# electronic_load_chip.net
KiCad netlist of a schematic drawn in EAGLE
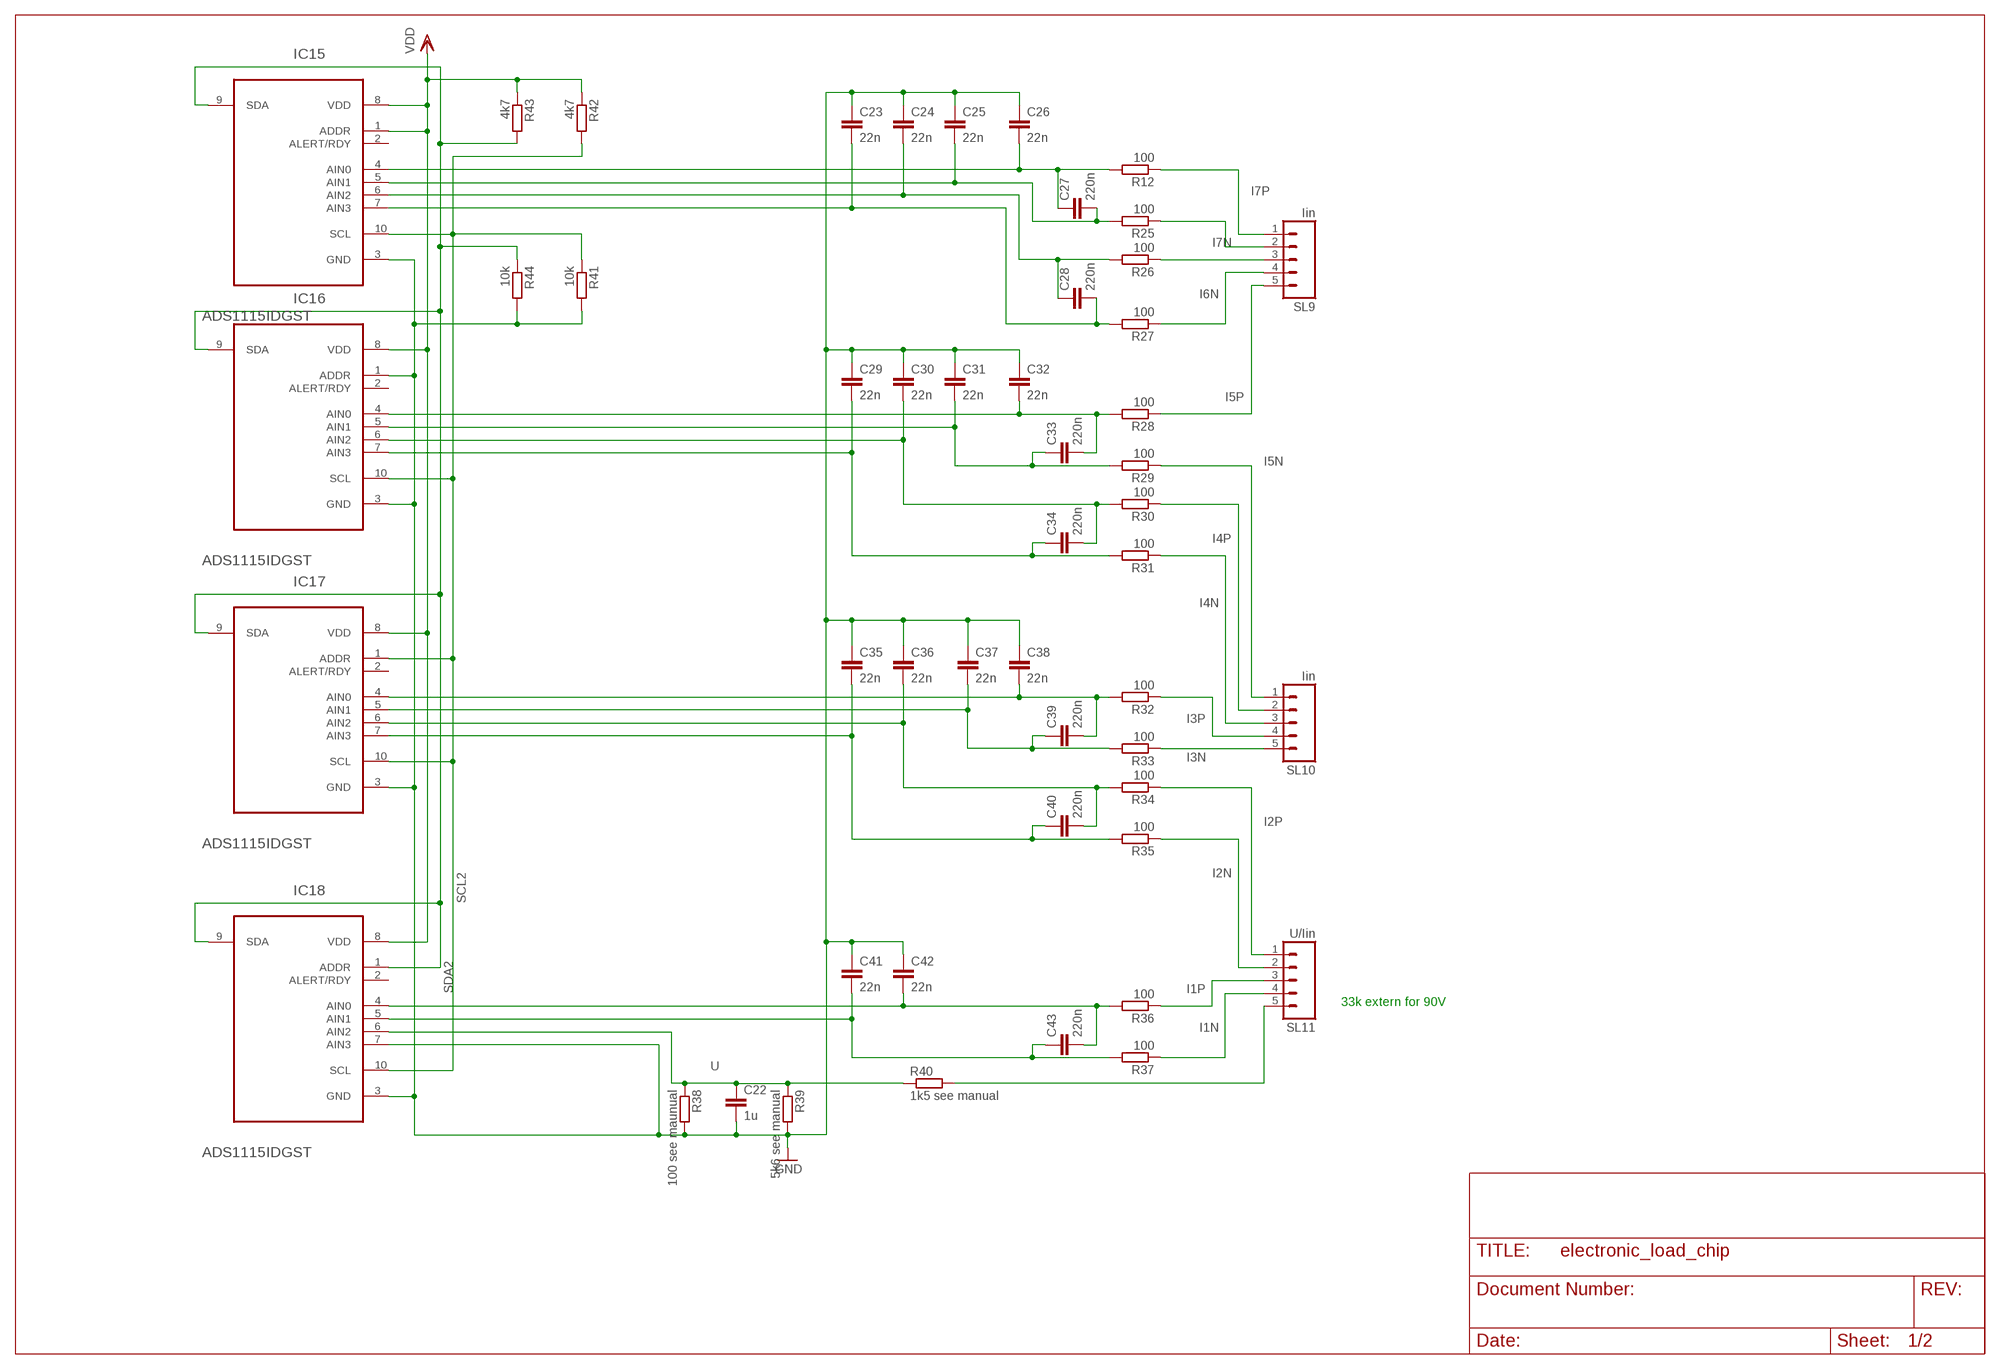
[diagram p0: schematic, sheet 1]
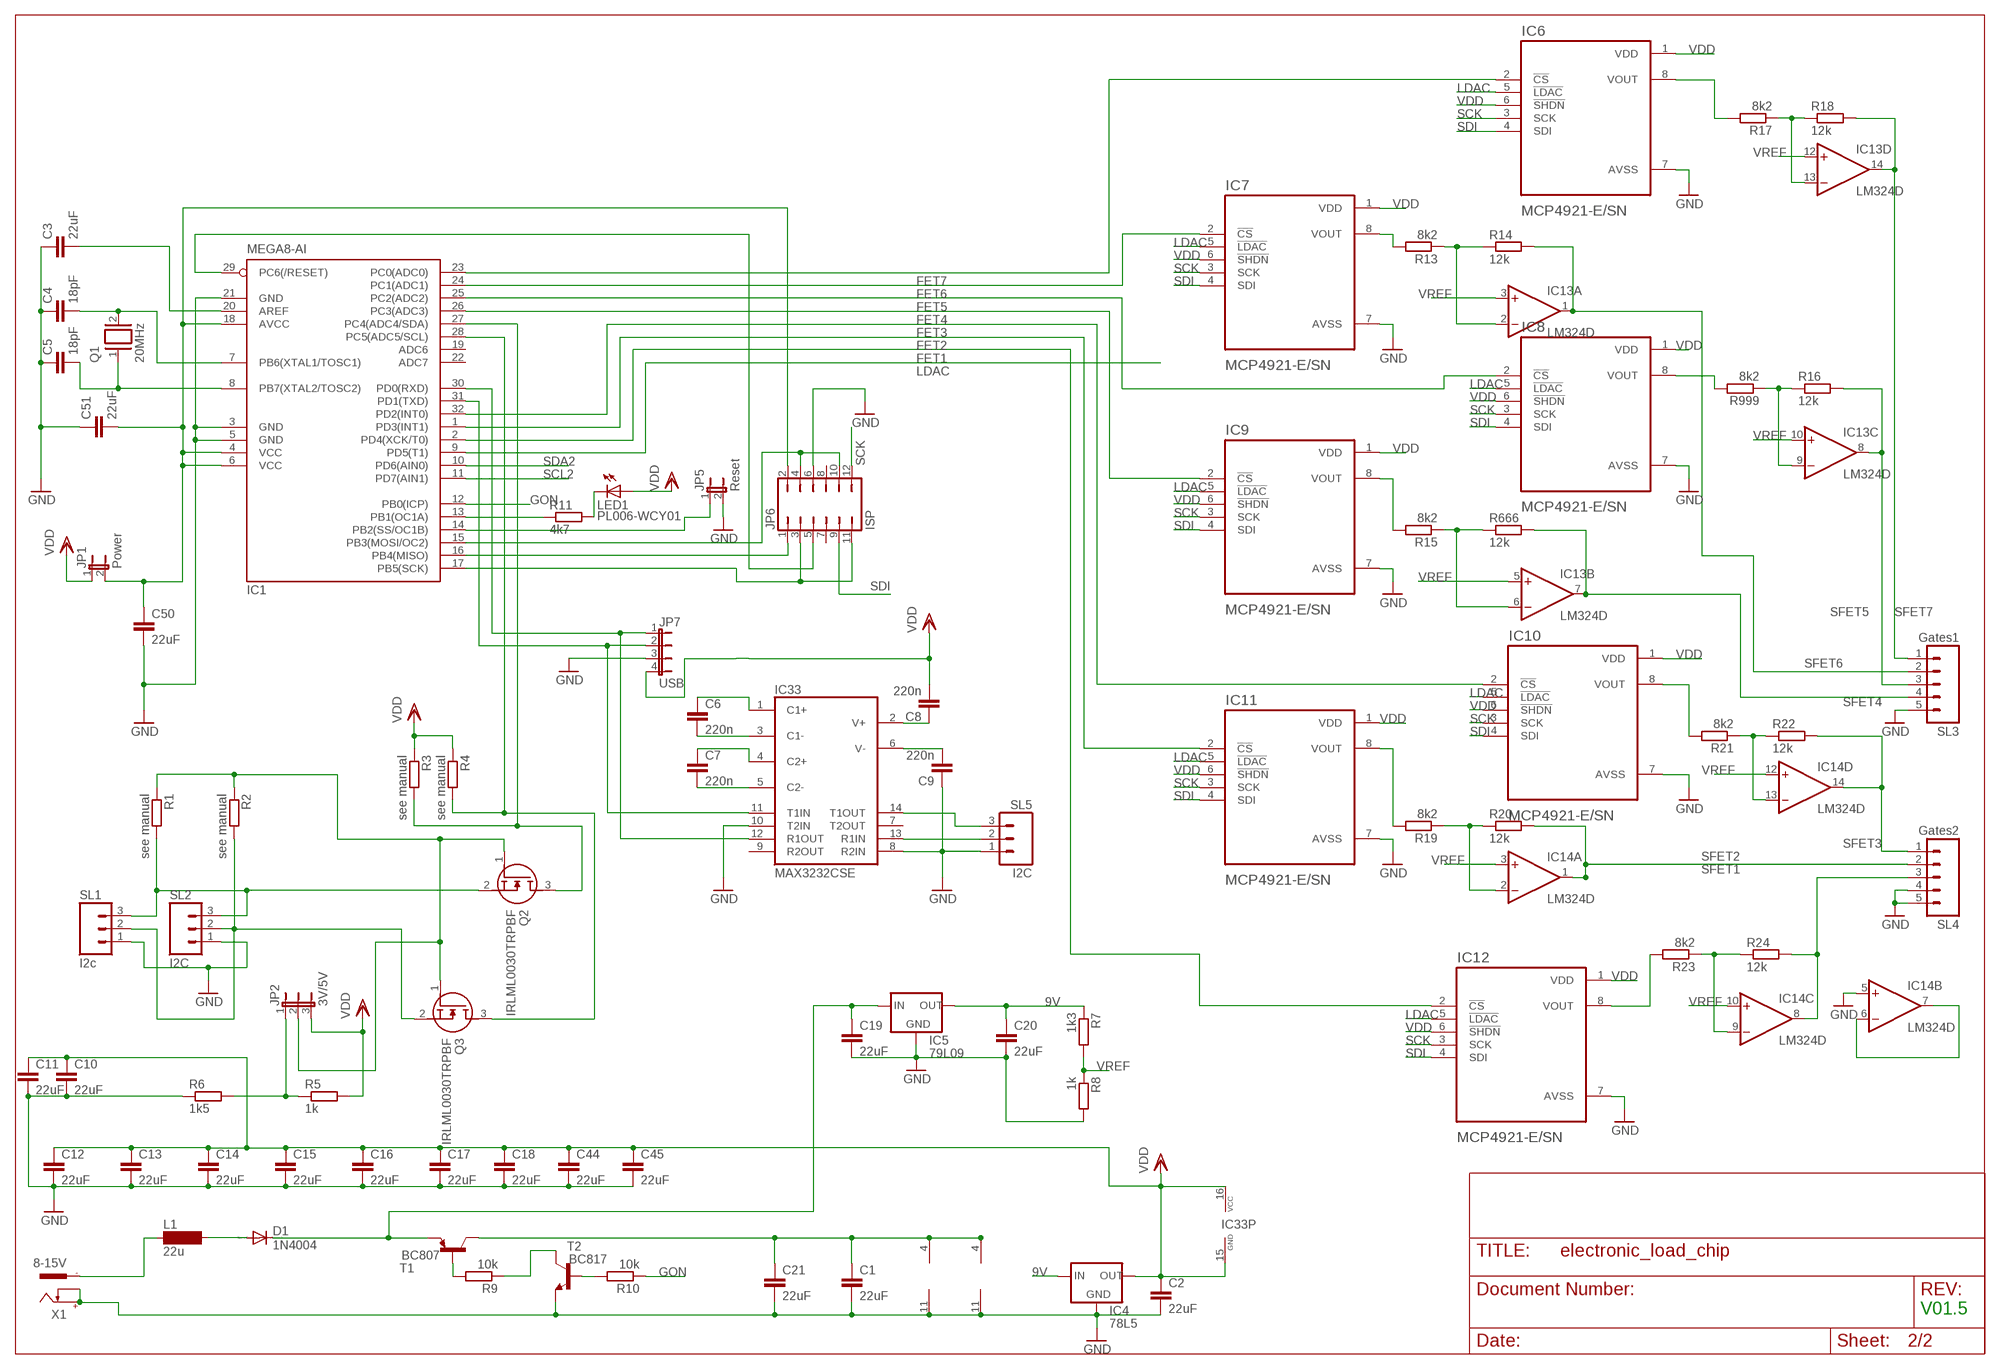
[diagram p1: schematic, sheet 2]

(export (version "E")
  (design (tool "Eeschema 10.0.6"))
  (components
    (comp (ref "C1")
      (value "22uF")
      (footprint "eagle-import:C1206")
      (libsource (lib "eagle-import") (part "C-EUC1206"))
    )
    (comp (ref "C2")
      (value "22uF")
      (footprint "eagle-import:C1206")
      (libsource (lib "eagle-import") (part "C-EUC1206"))
    )
    (comp (ref "C3")
      (value "22uF")
      (footprint "eagle-import:C1206")
      (libsource (lib "eagle-import") (part "C-EUC1206"))
    )
    (comp (ref "C4")
      (value "18pF")
      (footprint "eagle-import:C025-025X050")
      (libsource (lib "eagle-import") (part "resistor_C-EU025-025X050"))
    )
    (comp (ref "C5")
      (value "18pF")
      (footprint "eagle-import:C025-025X050")
      (libsource (lib "eagle-import") (part "resistor_C-EU025-025X050"))
    )
    (comp (ref "C6")
      (value "220n")
      (footprint "eagle-import:C1206")
      (libsource (lib "eagle-import") (part "C-EUC1206"))
    )
    (comp (ref "C7")
      (value "220n")
      (footprint "eagle-import:C1206")
      (libsource (lib "eagle-import") (part "C-EUC1206"))
    )
    (comp (ref "C8")
      (value "220n")
      (footprint "eagle-import:C1206")
      (libsource (lib "eagle-import") (part "C-EUC1206"))
    )
    (comp (ref "C9")
      (value "220n")
      (footprint "eagle-import:C1206")
      (libsource (lib "eagle-import") (part "C-EUC1206"))
    )
    (comp (ref "C10")
      (value "22uF")
      (footprint "eagle-import:C1206")
      (libsource (lib "eagle-import") (part "C-EUC1206"))
    )
    (comp (ref "C11")
      (value "22uF")
      (footprint "eagle-import:C1206")
      (libsource (lib "eagle-import") (part "C-EUC1206"))
    )
    (comp (ref "C12")
      (value "22uF")
      (footprint "eagle-import:C1206")
      (libsource (lib "eagle-import") (part "C-EUC1206"))
    )
    (comp (ref "C13")
      (value "22uF")
      (footprint "eagle-import:C1206")
      (libsource (lib "eagle-import") (part "C-EUC1206"))
    )
    (comp (ref "C14")
      (value "22uF")
      (footprint "eagle-import:C1206")
      (libsource (lib "eagle-import") (part "C-EUC1206"))
    )
    (comp (ref "C15")
      (value "22uF")
      (footprint "eagle-import:C1206")
      (libsource (lib "eagle-import") (part "C-EUC1206"))
    )
    (comp (ref "C16")
      (value "22uF")
      (footprint "eagle-import:C1206")
      (libsource (lib "eagle-import") (part "C-EUC1206"))
    )
    (comp (ref "C17")
      (value "22uF")
      (footprint "eagle-import:C1206")
      (libsource (lib "eagle-import") (part "C-EUC1206"))
    )
    (comp (ref "C18")
      (value "22uF")
      (footprint "eagle-import:C1206")
      (libsource (lib "eagle-import") (part "C-EUC1206"))
    )
    (comp (ref "C19")
      (value "22uF")
      (footprint "eagle-import:C1206")
      (libsource (lib "eagle-import") (part "C-EUC1206"))
    )
    (comp (ref "C20")
      (value "22uF")
      (footprint "eagle-import:C1206")
      (libsource (lib "eagle-import") (part "C-EUC1206"))
    )
    (comp (ref "C21")
      (value "22uF")
      (footprint "eagle-import:C1206")
      (libsource (lib "eagle-import") (part "C-EUC1206"))
    )
    (comp (ref "C44")
      (value "22uF")
      (footprint "eagle-import:C1206")
      (libsource (lib "eagle-import") (part "C-EUC1206"))
    )
    (comp (ref "C45")
      (value "22uF")
      (footprint "eagle-import:C1206")
      (libsource (lib "eagle-import") (part "C-EUC1206"))
    )
    (comp (ref "C50")
      (value "22uF")
      (footprint "eagle-import:C1206")
      (libsource (lib "eagle-import") (part "C-EUC1206"))
    )
    (comp (ref "C51")
      (value "22uF")
      (footprint "eagle-import:C1206")
      (libsource (lib "eagle-import") (part "C-EUC1206"))
    )
    (comp (ref "D1")
      (value "1N4004")
      (footprint "eagle-import:DO41-10")
      (libsource (lib "eagle-import") (part "1N4004"))
    )
    (comp (ref "IC1")
      (value "MEGA8-AI")
      (footprint "eagle-import:TQFP32-08")
      (fields (field (name "MPN") "ATMEGA8-16AU"))
      (libsource (lib "eagle-import") (part "MEGA8-AI"))
    )
    (comp (ref "IC4")
      (value "78L5")
      (footprint "eagle-import:78LXX")
      (libsource (lib "eagle-import") (part "78LXX"))
    )
    (comp (ref "IC5")
      (value "79L09")
      (footprint "eagle-import:78LXX")
      (libsource (lib "eagle-import") (part "78LXX"))
    )
    (comp (ref "IC6")
      (value "MCP4921-E/SN")
      (footprint "eagle-import:SOIC127P600X175-8N")
      (fields (field (name "MF") "Microchip"))
      (libsource (lib "eagle-import") (part "MCP4921-E/SN"))
    )
    (comp (ref "IC7")
      (value "MCP4921-E/SN")
      (footprint "eagle-import:SOIC127P600X175-8N")
      (fields (field (name "MF") "Microchip"))
      (libsource (lib "eagle-import") (part "MCP4921-E/SN"))
    )
    (comp (ref "IC8")
      (value "MCP4921-E/SN")
      (footprint "eagle-import:SOIC127P600X175-8N")
      (fields (field (name "MF") "Microchip"))
      (libsource (lib "eagle-import") (part "MCP4921-E/SN"))
    )
    (comp (ref "IC9")
      (value "MCP4921-E/SN")
      (footprint "eagle-import:SOIC127P600X175-8N")
      (fields (field (name "MF") "Microchip"))
      (libsource (lib "eagle-import") (part "MCP4921-E/SN"))
    )
    (comp (ref "IC10")
      (value "MCP4921-E/SN")
      (footprint "eagle-import:SOIC127P600X175-8N")
      (fields (field (name "MF") "Microchip"))
      (libsource (lib "eagle-import") (part "MCP4921-E/SN"))
    )
    (comp (ref "IC11")
      (value "MCP4921-E/SN")
      (footprint "eagle-import:SOIC127P600X175-8N")
      (fields (field (name "MF") "Microchip"))
      (libsource (lib "eagle-import") (part "MCP4921-E/SN"))
    )
    (comp (ref "IC12")
      (value "MCP4921-E/SN")
      (footprint "eagle-import:SOIC127P600X175-8N")
      (fields (field (name "MF") "Microchip"))
      (libsource (lib "eagle-import") (part "MCP4921-E/SN"))
    )
    (comp (ref "IC13")
      (value "LM324D")
      (footprint "eagle-import:SO14")
      (libsource (lib "eagle-import") (part "LM324D"))
    )
    (comp (ref "IC14")
      (value "LM324D")
      (footprint "eagle-import:SO14")
      (libsource (lib "eagle-import") (part "LM324D"))
    )
    (comp (ref "IC33")
      (value "MAX3232CSE")
      (footprint "eagle-import:SO16")
      (libsource (lib "eagle-import") (part "MAX3232SEC"))
    )
    (comp (ref "JP1")
      (value "Power")
      (footprint "eagle-import:JP1")
      (libsource (lib "eagle-import") (part "JP1E"))
    )
    (comp (ref "JP2")
      (value "3V/5V")
      (footprint "eagle-import:JP2")
      (libsource (lib "eagle-import") (part "JP2E"))
    )
    (comp (ref "JP5")
      (value "Reset")
      (footprint "eagle-import:JP1")
      (libsource (lib "eagle-import") (part "JP1E"))
    )
    (comp (ref "JP6")
      (value "ISP")
      (footprint "eagle-import:JP6Q")
      (libsource (lib "eagle-import") (part "JP6Q"))
    )
    (comp (ref "JP7")
      (value "USB")
      (footprint "eagle-import:JP4")
      (libsource (lib "eagle-import") (part "JP4E"))
    )
    (comp (ref "L1")
      (value "22u")
      (footprint "eagle-import:MS85")
      (libsource (lib "eagle-import") (part "MS85"))
    )
    (comp (ref "LED1")
      (value "PL006-WCY01")
      (footprint "eagle-import:SOT23")
      (libsource (lib "eagle-import") (part "PL006-WCY01"))
    )
    (comp (ref "Q1")
      (value "20MHz")
      (footprint "eagle-import:QS")
      (libsource (lib "eagle-import") (part "XTAL/S"))
    )
    (comp (ref "Q2")
      (value "IRLML0030TRPBF")
      (footprint "eagle-import:SOT95P237X112-3N")
      (fields (field (name "MF") "Infineon Technologies"))
      (libsource (lib "eagle-import") (part "IRLML0030TRPBF"))
    )
    (comp (ref "Q3")
      (value "IRLML0030TRPBF")
      (footprint "eagle-import:SOT95P237X112-3N")
      (fields (field (name "MF") "Infineon Technologies"))
      (libsource (lib "eagle-import") (part "IRLML0030TRPBF"))
    )
    (comp (ref "R1")
      (value "see manual")
      (footprint "eagle-import:R1206")
      (libsource (lib "eagle-import") (part "R-EU_R1206"))
    )
    (comp (ref "R2")
      (value "see manual")
      (footprint "eagle-import:R1206")
      (libsource (lib "eagle-import") (part "R-EU_R1206"))
    )
    (comp (ref "R3")
      (value "see manual")
      (footprint "eagle-import:R1206")
      (libsource (lib "eagle-import") (part "R-EU_R1206"))
    )
    (comp (ref "R4")
      (value "see manual")
      (footprint "eagle-import:R1206")
      (libsource (lib "eagle-import") (part "R-EU_R1206"))
    )
    (comp (ref "R5")
      (value "1k")
      (footprint "eagle-import:R1206")
      (libsource (lib "eagle-import") (part "R-EU_R1206"))
    )
    (comp (ref "R6")
      (value "1k5")
      (footprint "eagle-import:R1206")
      (libsource (lib "eagle-import") (part "R-EU_R1206"))
    )
    (comp (ref "R7")
      (value "1k3")
      (footprint "eagle-import:R1206")
      (libsource (lib "eagle-import") (part "R-EU_R1206"))
    )
    (comp (ref "R8")
      (value "1k")
      (footprint "eagle-import:R1206")
      (libsource (lib "eagle-import") (part "R-EU_R1206"))
    )
    (comp (ref "R9")
      (value "10k")
      (footprint "eagle-import:R1206")
      (libsource (lib "eagle-import") (part "R-EU_R1206"))
    )
    (comp (ref "R10")
      (value "10k")
      (footprint "eagle-import:R1206")
      (libsource (lib "eagle-import") (part "R-EU_R1206"))
    )
    (comp (ref "R11")
      (value "4k7")
      (footprint "eagle-import:R1206")
      (libsource (lib "eagle-import") (part "R-EU_R1206"))
    )
    (comp (ref "R13")
      (value "8k2")
      (footprint "eagle-import:R1206")
      (libsource (lib "eagle-import") (part "R-EU_R1206"))
    )
    (comp (ref "R14")
      (value "12k")
      (footprint "eagle-import:R1206")
      (libsource (lib "eagle-import") (part "R-EU_R1206"))
    )
    (comp (ref "R15")
      (value "8k2")
      (footprint "eagle-import:R1206")
      (libsource (lib "eagle-import") (part "R-EU_R1206"))
    )
    (comp (ref "R16")
      (value "12k")
      (footprint "eagle-import:R1206")
      (libsource (lib "eagle-import") (part "R-EU_R1206"))
    )
    (comp (ref "R17")
      (value "8k2")
      (footprint "eagle-import:R1206")
      (libsource (lib "eagle-import") (part "R-EU_R1206"))
    )
    (comp (ref "R18")
      (value "12k")
      (footprint "eagle-import:R1206")
      (libsource (lib "eagle-import") (part "R-EU_R1206"))
    )
    (comp (ref "R19")
      (value "8k2")
      (footprint "eagle-import:R1206")
      (libsource (lib "eagle-import") (part "R-EU_R1206"))
    )
    (comp (ref "R20")
      (value "12k")
      (footprint "eagle-import:R1206")
      (libsource (lib "eagle-import") (part "R-EU_R1206"))
    )
    (comp (ref "R21")
      (value "8k2")
      (footprint "eagle-import:R1206")
      (libsource (lib "eagle-import") (part "R-EU_R1206"))
    )
    (comp (ref "R22")
      (value "12k")
      (footprint "eagle-import:R1206")
      (libsource (lib "eagle-import") (part "R-EU_R1206"))
    )
    (comp (ref "R23")
      (value "8k2")
      (footprint "eagle-import:R1206")
      (libsource (lib "eagle-import") (part "R-EU_R1206"))
    )
    (comp (ref "R24")
      (value "12k")
      (footprint "eagle-import:R1206")
      (libsource (lib "eagle-import") (part "R-EU_R1206"))
    )
    (comp (ref "R666")
      (value "12k")
      (footprint "eagle-import:R1206")
      (libsource (lib "eagle-import") (part "R-EU_R1206"))
    )
    (comp (ref "R999")
      (value "8k2")
      (footprint "eagle-import:R1206")
      (libsource (lib "eagle-import") (part "R-EU_R1206"))
    )
    (comp (ref "SL1")
      (value "I2c")
      (footprint "eagle-import:03P")
      (libsource (lib "eagle-import") (part "M03"))
    )
    (comp (ref "SL2")
      (value "I2C")
      (footprint "eagle-import:03P")
      (libsource (lib "eagle-import") (part "M03"))
    )
    (comp (ref "SL3")
      (value "Gates1")
      (footprint "eagle-import:05P")
      (libsource (lib "eagle-import") (part "M05"))
    )
    (comp (ref "SL4")
      (value "Gates2")
      (footprint "eagle-import:05P")
      (libsource (lib "eagle-import") (part "M05"))
    )
    (comp (ref "SL5")
      (value "I2C")
      (footprint "eagle-import:03P")
      (libsource (lib "eagle-import") (part "M03"))
    )
    (comp (ref "T1")
      (value "BC807")
      (footprint "eagle-import:SOT23-BEC")
      (libsource (lib "eagle-import") (part "-PNP-SOT23-BECBC807-16"))
    )
    (comp (ref "T2")
      (value "BC817")
      (footprint "eagle-import:SOT23-BEC")
      (libsource (lib "eagle-import") (part "-NPN-SOT23-BECBC817-16"))
    )
    (comp (ref "X1")
      (value "8-15V")
      (footprint "eagle-import:737992-5")
      (libsource (lib "eagle-import") (part "737992-55"))
    )
    (comp (ref "C22")
      (value "1u")
      (footprint "eagle-import:C1206")
      (libsource (lib "eagle-import") (part "resistor_C-EUC1206"))
    )
    (comp (ref "C23")
      (value "22n")
      (footprint "eagle-import:C1206")
      (libsource (lib "eagle-import") (part "resistor_C-EUC1206"))
    )
    (comp (ref "C24")
      (value "22n")
      (footprint "eagle-import:C1206")
      (libsource (lib "eagle-import") (part "resistor_C-EUC1206"))
    )
    (comp (ref "C25")
      (value "22n")
      (footprint "eagle-import:C1206")
      (libsource (lib "eagle-import") (part "resistor_C-EUC1206"))
    )
    (comp (ref "C26")
      (value "22n")
      (footprint "eagle-import:C1206")
      (libsource (lib "eagle-import") (part "resistor_C-EUC1206"))
    )
    (comp (ref "C27")
      (value "220n")
      (footprint "eagle-import:C1206")
      (libsource (lib "eagle-import") (part "resistor_C-EUC1206"))
    )
    (comp (ref "C28")
      (value "220n")
      (footprint "eagle-import:C1206")
      (libsource (lib "eagle-import") (part "resistor_C-EUC1206"))
    )
    (comp (ref "C29")
      (value "22n")
      (footprint "eagle-import:C1206")
      (libsource (lib "eagle-import") (part "resistor_C-EUC1206"))
    )
    (comp (ref "C30")
      (value "22n")
      (footprint "eagle-import:C1206")
      (libsource (lib "eagle-import") (part "resistor_C-EUC1206"))
    )
    (comp (ref "C31")
      (value "22n")
      (footprint "eagle-import:C1206")
      (libsource (lib "eagle-import") (part "resistor_C-EUC1206"))
    )
    (comp (ref "C32")
      (value "22n")
      (footprint "eagle-import:C1206")
      (libsource (lib "eagle-import") (part "resistor_C-EUC1206"))
    )
    (comp (ref "C33")
      (value "220n")
      (footprint "eagle-import:C1206")
      (libsource (lib "eagle-import") (part "resistor_C-EUC1206"))
    )
    (comp (ref "C34")
      (value "220n")
      (footprint "eagle-import:C1206")
      (libsource (lib "eagle-import") (part "resistor_C-EUC1206"))
    )
    (comp (ref "C35")
      (value "22n")
      (footprint "eagle-import:C1206")
      (libsource (lib "eagle-import") (part "resistor_C-EUC1206"))
    )
    (comp (ref "C36")
      (value "22n")
      (footprint "eagle-import:C1206")
      (libsource (lib "eagle-import") (part "resistor_C-EUC1206"))
    )
    (comp (ref "C37")
      (value "22n")
      (footprint "eagle-import:C1206")
      (libsource (lib "eagle-import") (part "resistor_C-EUC1206"))
    )
    (comp (ref "C38")
      (value "22n")
      (footprint "eagle-import:C1206")
      (libsource (lib "eagle-import") (part "resistor_C-EUC1206"))
    )
    (comp (ref "C39")
      (value "220n")
      (footprint "eagle-import:C1206")
      (libsource (lib "eagle-import") (part "resistor_C-EUC1206"))
    )
    (comp (ref "C40")
      (value "220n")
      (footprint "eagle-import:C1206")
      (libsource (lib "eagle-import") (part "resistor_C-EUC1206"))
    )
    (comp (ref "C41")
      (value "22n")
      (footprint "eagle-import:C1206")
      (libsource (lib "eagle-import") (part "resistor_C-EUC1206"))
    )
    (comp (ref "C42")
      (value "22n")
      (footprint "eagle-import:C1206")
      (libsource (lib "eagle-import") (part "resistor_C-EUC1206"))
    )
    (comp (ref "C43")
      (value "220n")
      (footprint "eagle-import:C1206")
      (libsource (lib "eagle-import") (part "resistor_C-EUC1206"))
    )
    (comp (ref "IC15")
      (value "ADS1115IDGST")
      (footprint "eagle-import:SOP50P490X110-10N")
      (fields (field (name "MF") "Texas Instruments"))
      (libsource (lib "eagle-import") (part "ADS1115IDGST"))
    )
    (comp (ref "IC16")
      (value "ADS1115IDGST")
      (footprint "eagle-import:SOP50P490X110-10N")
      (fields (field (name "MF") "Texas Instruments"))
      (libsource (lib "eagle-import") (part "ADS1115IDGST"))
    )
    (comp (ref "IC17")
      (value "ADS1115IDGST")
      (footprint "eagle-import:SOP50P490X110-10N")
      (fields (field (name "MF") "Texas Instruments"))
      (libsource (lib "eagle-import") (part "ADS1115IDGST"))
    )
    (comp (ref "IC18")
      (value "ADS1115IDGST")
      (footprint "eagle-import:SOP50P490X110-10N")
      (fields (field (name "MF") "Texas Instruments"))
      (libsource (lib "eagle-import") (part "ADS1115IDGST"))
    )
    (comp (ref "R12")
      (value "100")
      (footprint "eagle-import:R1206")
      (libsource (lib "eagle-import") (part "R-EU_R1206"))
    )
    (comp (ref "R25")
      (value "100")
      (footprint "eagle-import:R1206")
      (libsource (lib "eagle-import") (part "R-EU_R1206"))
    )
    (comp (ref "R26")
      (value "100")
      (footprint "eagle-import:R1206")
      (libsource (lib "eagle-import") (part "R-EU_R1206"))
    )
    (comp (ref "R27")
      (value "100")
      (footprint "eagle-import:R1206")
      (libsource (lib "eagle-import") (part "R-EU_R1206"))
    )
    (comp (ref "R28")
      (value "100")
      (footprint "eagle-import:R1206")
      (libsource (lib "eagle-import") (part "R-EU_R1206"))
    )
    (comp (ref "R29")
      (value "100")
      (footprint "eagle-import:R1206")
      (libsource (lib "eagle-import") (part "R-EU_R1206"))
    )
    (comp (ref "R30")
      (value "100")
      (footprint "eagle-import:R1206")
      (libsource (lib "eagle-import") (part "R-EU_R1206"))
    )
    (comp (ref "R31")
      (value "100")
      (footprint "eagle-import:R1206")
      (libsource (lib "eagle-import") (part "R-EU_R1206"))
    )
    (comp (ref "R32")
      (value "100")
      (footprint "eagle-import:R1206")
      (libsource (lib "eagle-import") (part "R-EU_R1206"))
    )
    (comp (ref "R33")
      (value "100")
      (footprint "eagle-import:R1206")
      (libsource (lib "eagle-import") (part "R-EU_R1206"))
    )
    (comp (ref "R34")
      (value "100")
      (footprint "eagle-import:R1206")
      (libsource (lib "eagle-import") (part "R-EU_R1206"))
    )
    (comp (ref "R35")
      (value "100")
      (footprint "eagle-import:R1206")
      (libsource (lib "eagle-import") (part "R-EU_R1206"))
    )
    (comp (ref "R36")
      (value "100")
      (footprint "eagle-import:R1206")
      (libsource (lib "eagle-import") (part "R-EU_R1206"))
    )
    (comp (ref "R37")
      (value "100")
      (footprint "eagle-import:R1206")
      (libsource (lib "eagle-import") (part "R-EU_R1206"))
    )
    (comp (ref "R38")
      (value "100 see maunual")
      (footprint "eagle-import:R1206")
      (libsource (lib "eagle-import") (part "R-EU_R1206"))
    )
    (comp (ref "R39")
      (value "5k6 see manual")
      (footprint "eagle-import:R1206")
      (libsource (lib "eagle-import") (part "R-EU_R1206"))
    )
    (comp (ref "R40")
      (value "1k5 see manual")
      (footprint "eagle-import:R1206")
      (libsource (lib "eagle-import") (part "R-EU_R1206"))
    )
    (comp (ref "R41")
      (value "10k")
      (footprint "eagle-import:R1206")
      (libsource (lib "eagle-import") (part "R-EU_R1206"))
    )
    (comp (ref "R42")
      (value "4k7")
      (footprint "eagle-import:R1206")
      (libsource (lib "eagle-import") (part "R-EU_R1206"))
    )
    (comp (ref "R43")
      (value "4k7")
      (footprint "eagle-import:R1206")
      (libsource (lib "eagle-import") (part "R-EU_R1206"))
    )
    (comp (ref "R44")
      (value "10k")
      (footprint "eagle-import:R1206")
      (libsource (lib "eagle-import") (part "R-EU_R1206"))
    )
    (comp (ref "SL9")
      (value "Iin")
      (footprint "eagle-import:05P")
      (libsource (lib "eagle-import") (part "M05"))
    )
    (comp (ref "SL10")
      (value "Iin")
      (footprint "eagle-import:05P")
      (libsource (lib "eagle-import") (part "M05"))
    )
    (comp (ref "SL11")
      (value "U/Iin")
      (footprint "eagle-import:05P")
      (libsource (lib "eagle-import") (part "M05"))
    )
  )
  (nets
    (net (code "1") (name "9V") (class "Default")
      (node (ref "C20") (pin "1") (pinfunction "1_1") (pintype "passive"))
      (node (ref "IC4") (pin "IN") (pinfunction "IN_IN") (pintype "input"))
      (node (ref "IC5") (pin "OUT") (pinfunction "OUT_OUT") (pintype "passive"))
      (node (ref "R7") (pin "1") (pinfunction "1_1") (pintype "passive"))
    )
    (net (code "2") (name "FET1") (class "Default")
      (node (ref "IC1") (pin "2") (pinfunction "PD4(XCK/T0)_2") (pintype "bidirectional"))
      (node (ref "IC12") (pin "2") (pinfunction "~{CS}_2") (pintype "input"))
    )
    (net (code "3") (name "FET2") (class "Default")
      (node (ref "IC1") (pin "1") (pinfunction "PD3(INT1)_1") (pintype "bidirectional"))
      (node (ref "IC11") (pin "2") (pinfunction "~{CS}_2") (pintype "input"))
    )
    (net (code "4") (name "FET3") (class "Default")
      (node (ref "IC1") (pin "32") (pinfunction "PD2(INT0)_32") (pintype "bidirectional"))
      (node (ref "IC10") (pin "2") (pinfunction "~{CS}_2") (pintype "input"))
    )
    (net (code "5") (name "FET4") (class "Default")
      (node (ref "IC1") (pin "26") (pinfunction "PC3(ADC3)_26") (pintype "bidirectional"))
      (node (ref "IC9") (pin "2") (pinfunction "~{CS}_2") (pintype "input"))
    )
    (net (code "6") (name "FET5") (class "Default")
      (node (ref "IC1") (pin "25") (pinfunction "PC2(ADC2)_25") (pintype "bidirectional"))
      (node (ref "IC8") (pin "2") (pinfunction "~{CS}_2") (pintype "input"))
    )
    (net (code "7") (name "FET6") (class "Default")
      (node (ref "IC1") (pin "24") (pinfunction "PC1(ADC1)_24") (pintype "bidirectional"))
      (node (ref "IC7") (pin "2") (pinfunction "~{CS}_2") (pintype "input"))
    )
    (net (code "8") (name "FET7") (class "Default")
      (node (ref "IC1") (pin "23") (pinfunction "PC0(ADC0)_23") (pintype "bidirectional"))
      (node (ref "IC6") (pin "2") (pinfunction "~{CS}_2") (pintype "input"))
    )
    (net (code "9") (name "GND") (class "Default")
      (node (ref "C1") (pin "2") (pinfunction "2_2") (pintype "passive"))
      (node (ref "C10") (pin "2") (pinfunction "2_2") (pintype "passive"))
      (node (ref "C11") (pin "2") (pinfunction "2_2") (pintype "passive"))
      (node (ref "C12") (pin "2") (pinfunction "2_2") (pintype "passive"))
      (node (ref "C13") (pin "2") (pinfunction "2_2") (pintype "passive"))
      (node (ref "C14") (pin "2") (pinfunction "2_2") (pintype "passive"))
      (node (ref "C15") (pin "2") (pinfunction "2_2") (pintype "passive"))
      (node (ref "C16") (pin "2") (pinfunction "2_2") (pintype "passive"))
      (node (ref "C17") (pin "2") (pinfunction "2_2") (pintype "passive"))
      (node (ref "C18") (pin "2") (pinfunction "2_2") (pintype "passive"))
      (node (ref "C19") (pin "2") (pinfunction "2_2") (pintype "passive"))
      (node (ref "C2") (pin "2") (pinfunction "2_2") (pintype "passive"))
      (node (ref "C20") (pin "2") (pinfunction "2_2") (pintype "passive"))
      (node (ref "C21") (pin "2") (pinfunction "2_2") (pintype "passive"))
      (node (ref "C22") (pin "2") (pinfunction "2_2") (pintype "passive"))
      (node (ref "C23") (pin "1") (pinfunction "1_1") (pintype "passive"))
      (node (ref "C24") (pin "1") (pinfunction "1_1") (pintype "passive"))
      (node (ref "C25") (pin "1") (pinfunction "1_1") (pintype "passive"))
      (node (ref "C26") (pin "1") (pinfunction "1_1") (pintype "passive"))
      (node (ref "C29") (pin "1") (pinfunction "1_1") (pintype "passive"))
      (node (ref "C3") (pin "1") (pinfunction "1_1") (pintype "passive"))
      (node (ref "C30") (pin "1") (pinfunction "1_1") (pintype "passive"))
      (node (ref "C31") (pin "1") (pinfunction "1_1") (pintype "passive"))
      (node (ref "C32") (pin "1") (pinfunction "1_1") (pintype "passive"))
      (node (ref "C35") (pin "1") (pinfunction "1_1") (pintype "passive"))
      (node (ref "C36") (pin "1") (pinfunction "1_1") (pintype "passive"))
      (node (ref "C37") (pin "1") (pinfunction "1_1") (pintype "passive"))
      (node (ref "C38") (pin "1") (pinfunction "1_1") (pintype "passive"))
      (node (ref "C4") (pin "1") (pinfunction "1_1") (pintype "passive"))
      (node (ref "C41") (pin "1") (pinfunction "1_1") (pintype "passive"))
      (node (ref "C42") (pin "1") (pinfunction "1_1") (pintype "passive"))
      (node (ref "C44") (pin "2") (pinfunction "2_2") (pintype "passive"))
      (node (ref "C45") (pin "2") (pinfunction "2_2") (pintype "passive"))
      (node (ref "C5") (pin "1") (pinfunction "1_1") (pintype "passive"))
      (node (ref "C50") (pin "2") (pinfunction "2_2") (pintype "passive"))
      (node (ref "C51") (pin "1") (pinfunction "1_1") (pintype "passive"))
      (node (ref "C9") (pin "1") (pinfunction "1_1") (pintype "passive"))
      (node (ref "IC1") (pin "21") (pinfunction "GND_21") (pintype "power_in"))
      (node (ref "IC1") (pin "3") (pinfunction "GND_3") (pintype "power_in"))
      (node (ref "IC1") (pin "5") (pinfunction "GND_5") (pintype "power_in"))
      (node (ref "IC10") (pin "7") (pinfunction "AVSS_7") (pintype "power_in"))
      (node (ref "IC11") (pin "7") (pinfunction "AVSS_7") (pintype "power_in"))
      (node (ref "IC12") (pin "7") (pinfunction "AVSS_7") (pintype "power_in"))
      (node (ref "IC13") (pin "11") (pinfunction "V-_11") (pintype "power_in"))
      (node (ref "IC14") (pin "11") (pinfunction "V-_11") (pintype "power_in"))
      (node (ref "IC14") (pin "5") (pinfunction "+IN_5") (pintype "input"))
      (node (ref "IC15") (pin "3") (pinfunction "GND_3") (pintype "passive"))
      (node (ref "IC16") (pin "1") (pinfunction "ADDR_1") (pintype "input"))
      (node (ref "IC16") (pin "3") (pinfunction "GND_3") (pintype "passive"))
      (node (ref "IC17") (pin "3") (pinfunction "GND_3") (pintype "passive"))
      (node (ref "IC18") (pin "3") (pinfunction "GND_3") (pintype "passive"))
      (node (ref "IC18") (pin "7") (pinfunction "AIN3_7") (pintype "input"))
      (node (ref "IC33") (pin "10") (pinfunction "T2IN_10") (pintype "input"))
      (node (ref "IC33") (pin "8") (pinfunction "R2IN_8") (pintype "input"))
      (node (ref "IC4") (pin "GND") (pinfunction "GND_GND") (pintype "input"))
      (node (ref "IC5") (pin "GND") (pinfunction "GND_GND") (pintype "input"))
      (node (ref "IC6") (pin "7") (pinfunction "AVSS_7") (pintype "power_in"))
      (node (ref "IC7") (pin "7") (pinfunction "AVSS_7") (pintype "power_in"))
      (node (ref "IC8") (pin "7") (pinfunction "AVSS_7") (pintype "power_in"))
      (node (ref "IC9") (pin "7") (pinfunction "AVSS_7") (pintype "power_in"))
      (node (ref "JP5") (pin "2") (pinfunction "2_2") (pintype "passive"))
      (node (ref "JP6") (pin "6") (pinfunction "6_6") (pintype "passive"))
      (node (ref "JP7") (pin "3") (pinfunction "3_3") (pintype "passive"))
      (node (ref "R38") (pin "2") (pinfunction "2_2") (pintype "passive"))
      (node (ref "R39") (pin "2") (pinfunction "2_2") (pintype "passive"))
      (node (ref "R41") (pin "2") (pinfunction "2_2") (pintype "passive"))
      (node (ref "R44") (pin "2") (pinfunction "2_2") (pintype "passive"))
      (node (ref "R6") (pin "1") (pinfunction "1_1") (pintype "passive"))
      (node (ref "R8") (pin "2") (pinfunction "2_2") (pintype "passive"))
      (node (ref "SL1") (pin "1") (pinfunction "1_1") (pintype "passive"))
      (node (ref "SL2") (pin "1") (pinfunction "1_1") (pintype "passive"))
      (node (ref "SL3") (pin "5") (pinfunction "5_5") (pintype "passive"))
      (node (ref "SL4") (pin "4") (pinfunction "4_4") (pintype "passive"))
      (node (ref "SL4") (pin "5") (pinfunction "5_5") (pintype "passive"))
      (node (ref "SL5") (pin "1") (pinfunction "1_1") (pintype "passive"))
      (node (ref "T2") (pin "E") (pinfunction "E_E") (pintype "passive"))
      (node (ref "X1") (pin "+") (pinfunction "+_+") (pintype "passive"))
      (node (ref "X1") (pin "K") (pinfunction "K_K") (pintype "passive"))
    )
    (net (code "10") (name "GON") (class "Default")
      (node (ref "IC1") (pin "12") (pinfunction "PB0(ICP)_12") (pintype "bidirectional"))
      (node (ref "R10") (pin "1") (pinfunction "1_1") (pintype "passive"))
    )
    (net (code "11") (name "I1N") (class "Default")
      (node (ref "R37") (pin "1") (pinfunction "1_1") (pintype "passive"))
      (node (ref "SL11") (pin "4") (pinfunction "4_4") (pintype "passive"))
    )
    (net (code "12") (name "I1P") (class "Default")
      (node (ref "R36") (pin "1") (pinfunction "1_1") (pintype "passive"))
      (node (ref "SL11") (pin "3") (pinfunction "3_3") (pintype "passive"))
    )
    (net (code "13") (name "I2N") (class "Default")
      (node (ref "R35") (pin "1") (pinfunction "1_1") (pintype "passive"))
      (node (ref "SL11") (pin "2") (pinfunction "2_2") (pintype "passive"))
    )
    (net (code "14") (name "I2P") (class "Default")
      (node (ref "R34") (pin "1") (pinfunction "1_1") (pintype "passive"))
      (node (ref "SL11") (pin "1") (pinfunction "1_1") (pintype "passive"))
    )
    (net (code "15") (name "I3N") (class "Default")
      (node (ref "R33") (pin "1") (pinfunction "1_1") (pintype "passive"))
      (node (ref "SL10") (pin "5") (pinfunction "5_5") (pintype "passive"))
    )
    (net (code "16") (name "I3P") (class "Default")
      (node (ref "R32") (pin "1") (pinfunction "1_1") (pintype "passive"))
      (node (ref "SL10") (pin "4") (pinfunction "4_4") (pintype "passive"))
    )
    (net (code "17") (name "I4N") (class "Default")
      (node (ref "R31") (pin "1") (pinfunction "1_1") (pintype "passive"))
      (node (ref "SL10") (pin "3") (pinfunction "3_3") (pintype "passive"))
    )
    (net (code "18") (name "I4P") (class "Default")
      (node (ref "R30") (pin "1") (pinfunction "1_1") (pintype "passive"))
      (node (ref "SL10") (pin "2") (pinfunction "2_2") (pintype "passive"))
    )
    (net (code "19") (name "I5N") (class "Default")
      (node (ref "R29") (pin "1") (pinfunction "1_1") (pintype "passive"))
      (node (ref "SL10") (pin "1") (pinfunction "1_1") (pintype "passive"))
    )
    (net (code "20") (name "I5P") (class "Default")
      (node (ref "R28") (pin "1") (pinfunction "1_1") (pintype "passive"))
      (node (ref "SL9") (pin "5") (pinfunction "5_5") (pintype "passive"))
    )
    (net (code "21") (name "I6N") (class "Default")
      (node (ref "R27") (pin "1") (pinfunction "1_1") (pintype "passive"))
      (node (ref "SL9") (pin "4") (pinfunction "4_4") (pintype "passive"))
    )
    (net (code "22") (name "I7N") (class "Default")
      (node (ref "R25") (pin "1") (pinfunction "1_1") (pintype "passive"))
      (node (ref "SL9") (pin "2") (pinfunction "2_2") (pintype "passive"))
    )
    (net (code "23") (name "I7P") (class "Default")
      (node (ref "R12") (pin "1") (pinfunction "1_1") (pintype "passive"))
      (node (ref "SL9") (pin "1") (pinfunction "1_1") (pintype "passive"))
    )
    (net (code "24") (name "LDAC") (class "Default")
      (node (ref "IC1") (pin "9") (pinfunction "PD5(T1)_9") (pintype "bidirectional"))
      (node (ref "IC10") (pin "5") (pinfunction "~{LDAC}_5") (pintype "input"))
      (node (ref "IC11") (pin "5") (pinfunction "~{LDAC}_5") (pintype "input"))
      (node (ref "IC12") (pin "5") (pinfunction "~{LDAC}_5") (pintype "input"))
      (node (ref "IC6") (pin "5") (pinfunction "~{LDAC}_5") (pintype "input"))
      (node (ref "IC7") (pin "5") (pinfunction "~{LDAC}_5") (pintype "input"))
      (node (ref "IC8") (pin "5") (pinfunction "~{LDAC}_5") (pintype "input"))
      (node (ref "IC9") (pin "5") (pinfunction "~{LDAC}_5") (pintype "input"))
    )
    (net (code "25") (name "Net-(C19-Pad1)") (class "Default")
      (node (ref "C19") (pin "1") (pinfunction "1_1") (pintype "passive"))
      (node (ref "D1") (pin "C") (pinfunction "C_C") (pintype "passive"))
      (node (ref "IC5") (pin "IN") (pinfunction "IN_IN") (pintype "input"))
      (node (ref "T1") (pin "E") (pinfunction "E_E") (pintype "passive"))
    )
    (net (code "26") (name "Net-(D1-PadA)") (class "Default")
      (node (ref "D1") (pin "A") (pinfunction "A_A") (pintype "passive"))
      (node (ref "L1") (pin "2") (pinfunction "2_2") (pintype "passive"))
    )
    (net (code "27") (name "Net-(IC1-AREF)") (class "Default")
      (node (ref "C3") (pin "2") (pinfunction "2_2") (pintype "passive"))
      (node (ref "IC1") (pin "20") (pinfunction "AREF_20") (pintype "passive"))
    )
    (net (code "28") (name "Net-(IC1-AVCC)") (class "Default")
      (node (ref "C50") (pin "1") (pinfunction "1_1") (pintype "passive"))
      (node (ref "C51") (pin "2") (pinfunction "2_2") (pintype "passive"))
      (node (ref "IC1") (pin "18") (pinfunction "AVCC_18") (pintype "power_in"))
      (node (ref "IC1") (pin "4") (pinfunction "VCC_4") (pintype "power_in"))
      (node (ref "IC1") (pin "6") (pinfunction "VCC_6") (pintype "power_in"))
      (node (ref "JP1") (pin "2") (pinfunction "2_2") (pintype "passive"))
      (node (ref "JP6") (pin "2") (pinfunction "2_2") (pintype "passive"))
    )
    (net (code "29") (name "Net-(IC1-PB1(OC1A))") (class "Default")
      (node (ref "IC1") (pin "13") (pinfunction "PB1(OC1A)_13") (pintype "bidirectional"))
      (node (ref "R11") (pin "1") (pinfunction "1_1") (pintype "passive"))
    )
    (net (code "30") (name "Net-(IC1-PB2(SS{slash}OC1B))") (class "Default")
      (node (ref "IC1") (pin "14") (pinfunction "PB2(SS/OC1B)_14") (pintype "bidirectional"))
      (node (ref "JP5") (pin "1") (pinfunction "1_1") (pintype "passive"))
    )
    (net (code "31") (name "Net-(IC1-PB3(MOSI{slash}OC2))") (class "Default")
      (node (ref "IC1") (pin "15") (pinfunction "PB3(MOSI/OC2)_15") (pintype "bidirectional"))
      (node (ref "JP6") (pin "10") (pinfunction "10_10") (pintype "passive"))
      (node (ref "JP6") (pin "4") (pinfunction "4_4") (pintype "passive"))
    )
    (net (code "32") (name "Net-(IC1-PB4(MISO))") (class "Default")
      (node (ref "IC1") (pin "16") (pinfunction "PB4(MISO)_16") (pintype "bidirectional"))
      (node (ref "JP6") (pin "1") (pinfunction "1_1") (pintype "passive"))
    )
    (net (code "33") (name "Net-(IC1-PB5(SCK))") (class "Default")
      (node (ref "IC1") (pin "17") (pinfunction "PB5(SCK)_17") (pintype "bidirectional"))
      (node (ref "JP6") (pin "11") (pinfunction "11_11") (pintype "passive"))
      (node (ref "JP6") (pin "3") (pinfunction "3_3") (pintype "passive"))
    )
    (net (code "34") (name "Net-(IC1-PB6(XTAL1{slash}TOSC1))") (class "Default")
      (node (ref "C4") (pin "2") (pinfunction "2_2") (pintype "passive"))
      (node (ref "IC1") (pin "7") (pinfunction "PB6(XTAL1/TOSC1)_7") (pintype "bidirectional"))
      (node (ref "Q1") (pin "2") (pinfunction "2_2") (pintype "passive"))
    )
    (net (code "35") (name "Net-(IC1-PB7(XTAL2{slash}TOSC2))") (class "Default")
      (node (ref "C5") (pin "2") (pinfunction "2_2") (pintype "passive"))
      (node (ref "IC1") (pin "8") (pinfunction "PB7(XTAL2/TOSC2)_8") (pintype "bidirectional"))
      (node (ref "Q1") (pin "1") (pinfunction "1_1") (pintype "passive"))
    )
    (net (code "36") (name "Net-(IC1-PC4(ADC4{slash}SDA))") (class "Default")
      (node (ref "IC1") (pin "27") (pinfunction "PC4(ADC4/SDA)_27") (pintype "bidirectional"))
      (node (ref "Q2") (pin "3") (pinfunction "D_3") (pintype "bidirectional"))
      (node (ref "R3") (pin "2") (pinfunction "2_2") (pintype "passive"))
    )
    (net (code "37") (name "Net-(IC1-PC5(ADC5{slash}SCL))") (class "Default")
      (node (ref "IC1") (pin "28") (pinfunction "PC5(ADC5/SCL)_28") (pintype "bidirectional"))
      (node (ref "Q3") (pin "3") (pinfunction "D_3") (pintype "bidirectional"))
      (node (ref "R4") (pin "2") (pinfunction "2_2") (pintype "passive"))
    )
    (net (code "38") (name "Net-(IC1-PC6({slash}RESET))") (class "Default")
      (node (ref "IC1") (pin "29") (pinfunction "PC6(/RESET)_29") (pintype "bidirectional"))
      (node (ref "JP6") (pin "5") (pinfunction "5_5") (pintype "passive"))
    )
    (net (code "39") (name "Net-(IC1-PD0(RXD))") (class "Default")
      (node (ref "IC1") (pin "30") (pinfunction "PD0(RXD)_30") (pintype "bidirectional"))
      (node (ref "IC33") (pin "12") (pinfunction "R1OUT_12") (pintype "output"))
      (node (ref "JP7") (pin "1") (pinfunction "1_1") (pintype "passive"))
    )
    (net (code "40") (name "Net-(IC1-PD1(TXD))") (class "Default")
      (node (ref "IC1") (pin "31") (pinfunction "PD1(TXD)_31") (pintype "bidirectional"))
      (node (ref "IC33") (pin "11") (pinfunction "T1IN_11") (pintype "input"))
      (node (ref "JP7") (pin "2") (pinfunction "2_2") (pintype "passive"))
    )
    (net (code "41") (name "Net-(IC6-VOUT)") (class "Default")
      (node (ref "IC6") (pin "8") (pinfunction "VOUT_8") (pintype "output"))
      (node (ref "R17") (pin "2") (pinfunction "2_2") (pintype "passive"))
    )
    (net (code "42") (name "Net-(IC7-VOUT)") (class "Default")
      (node (ref "IC7") (pin "8") (pinfunction "VOUT_8") (pintype "output"))
      (node (ref "R13") (pin "2") (pinfunction "2_2") (pintype "passive"))
    )
    (net (code "43") (name "Net-(IC8-VOUT)") (class "Default")
      (node (ref "IC8") (pin "8") (pinfunction "VOUT_8") (pintype "output"))
      (node (ref "R999") (pin "2") (pinfunction "2_2") (pintype "passive"))
    )
    (net (code "44") (name "Net-(IC9-VOUT)") (class "Default")
      (node (ref "IC9") (pin "8") (pinfunction "VOUT_8") (pintype "output"))
      (node (ref "R15") (pin "2") (pinfunction "2_2") (pintype "passive"))
    )
    (net (code "45") (name "Net-(IC10-VOUT)") (class "Default")
      (node (ref "IC10") (pin "8") (pinfunction "VOUT_8") (pintype "output"))
      (node (ref "R21") (pin "2") (pinfunction "2_2") (pintype "passive"))
    )
    (net (code "46") (name "Net-(IC11-VOUT)") (class "Default")
      (node (ref "IC11") (pin "8") (pinfunction "VOUT_8") (pintype "output"))
      (node (ref "R19") (pin "2") (pinfunction "2_2") (pintype "passive"))
    )
    (net (code "47") (name "Net-(IC12-VOUT)") (class "Default")
      (node (ref "IC12") (pin "8") (pinfunction "VOUT_8") (pintype "output"))
      (node (ref "R23") (pin "2") (pinfunction "2_2") (pintype "passive"))
    )
    (net (code "48") (name "Net-(IC13A--IN)") (class "Default")
      (node (ref "IC13") (pin "2") (pinfunction "-IN_2") (pintype "input"))
      (node (ref "R13") (pin "1") (pinfunction "1_1") (pintype "passive"))
      (node (ref "R14") (pin "1") (pinfunction "1_1") (pintype "passive"))
    )
    (net (code "49") (name "Net-(IC13B--IN)") (class "Default")
      (node (ref "IC13") (pin "6") (pinfunction "-IN_6") (pintype "input"))
      (node (ref "R15") (pin "1") (pinfunction "1_1") (pintype "passive"))
      (node (ref "R666") (pin "1") (pinfunction "1_1") (pintype "passive"))
    )
    (net (code "50") (name "Net-(IC13C--IN)") (class "Default")
      (node (ref "IC13") (pin "9") (pinfunction "-IN_9") (pintype "input"))
      (node (ref "R16") (pin "1") (pinfunction "1_1") (pintype "passive"))
      (node (ref "R999") (pin "1") (pinfunction "1_1") (pintype "passive"))
    )
    (net (code "51") (name "Net-(IC13D--IN)") (class "Default")
      (node (ref "IC13") (pin "13") (pinfunction "-IN_13") (pintype "input"))
      (node (ref "R17") (pin "1") (pinfunction "1_1") (pintype "passive"))
      (node (ref "R18") (pin "1") (pinfunction "1_1") (pintype "passive"))
    )
    (net (code "52") (name "Net-(IC13E-V+)") (class "Default")
      (node (ref "C1") (pin "1") (pinfunction "1_1") (pintype "passive"))
      (node (ref "C21") (pin "1") (pinfunction "1_1") (pintype "passive"))
      (node (ref "IC13") (pin "4") (pinfunction "V+_4") (pintype "power_in"))
      (node (ref "IC14") (pin "4") (pinfunction "V+_4") (pintype "power_in"))
      (node (ref "T1") (pin "C") (pinfunction "C_C") (pintype "passive"))
    )
    (net (code "53") (name "Net-(IC14A--IN)") (class "Default")
      (node (ref "IC14") (pin "2") (pinfunction "-IN_2") (pintype "input"))
      (node (ref "R19") (pin "1") (pinfunction "1_1") (pintype "passive"))
      (node (ref "R20") (pin "1") (pinfunction "1_1") (pintype "passive"))
    )
    (net (code "54") (name "Net-(IC14B--IN)") (class "Default")
      (node (ref "IC14") (pin "6") (pinfunction "-IN_6") (pintype "input"))
      (node (ref "IC14") (pin "7") (pinfunction "OUT_7") (pintype "output"))
    )
    (net (code "55") (name "Net-(IC14C--IN)") (class "Default")
      (node (ref "IC14") (pin "9") (pinfunction "-IN_9") (pintype "input"))
      (node (ref "R23") (pin "1") (pinfunction "1_1") (pintype "passive"))
      (node (ref "R24") (pin "1") (pinfunction "1_1") (pintype "passive"))
    )
    (net (code "56") (name "Net-(IC14D--IN)") (class "Default")
      (node (ref "IC14") (pin "13") (pinfunction "-IN_13") (pintype "input"))
      (node (ref "R21") (pin "1") (pinfunction "1_1") (pintype "passive"))
      (node (ref "R22") (pin "1") (pinfunction "1_1") (pintype "passive"))
    )
    (net (code "57") (name "Net-(IC15-AIN0)") (class "Default")
      (node (ref "C26") (pin "2") (pinfunction "2_2") (pintype "passive"))
      (node (ref "C27") (pin "1") (pinfunction "1_1") (pintype "passive"))
      (node (ref "IC15") (pin "4") (pinfunction "AIN0_4") (pintype "input"))
      (node (ref "R12") (pin "2") (pinfunction "2_2") (pintype "passive"))
    )
    (net (code "58") (name "Net-(IC15-AIN1)") (class "Default")
      (node (ref "C25") (pin "2") (pinfunction "2_2") (pintype "passive"))
      (node (ref "C27") (pin "2") (pinfunction "2_2") (pintype "passive"))
      (node (ref "IC15") (pin "5") (pinfunction "AIN1_5") (pintype "input"))
      (node (ref "R25") (pin "2") (pinfunction "2_2") (pintype "passive"))
    )
    (net (code "59") (name "Net-(IC15-AIN2)") (class "Default")
      (node (ref "C24") (pin "2") (pinfunction "2_2") (pintype "passive"))
      (node (ref "C28") (pin "1") (pinfunction "1_1") (pintype "passive"))
      (node (ref "IC15") (pin "6") (pinfunction "AIN2_6") (pintype "input"))
      (node (ref "R26") (pin "2") (pinfunction "2_2") (pintype "passive"))
    )
    (net (code "60") (name "Net-(IC15-AIN3)") (class "Default")
      (node (ref "C23") (pin "2") (pinfunction "2_2") (pintype "passive"))
      (node (ref "C28") (pin "2") (pinfunction "2_2") (pintype "passive"))
      (node (ref "IC15") (pin "7") (pinfunction "AIN3_7") (pintype "input"))
      (node (ref "R27") (pin "2") (pinfunction "2_2") (pintype "passive"))
    )
    (net (code "61") (name "Net-(IC16-AIN0)") (class "Default")
      (node (ref "C32") (pin "2") (pinfunction "2_2") (pintype "passive"))
      (node (ref "C33") (pin "2") (pinfunction "2_2") (pintype "passive"))
      (node (ref "IC16") (pin "4") (pinfunction "AIN0_4") (pintype "input"))
      (node (ref "R28") (pin "2") (pinfunction "2_2") (pintype "passive"))
    )
    (net (code "62") (name "Net-(IC16-AIN1)") (class "Default")
      (node (ref "C31") (pin "2") (pinfunction "2_2") (pintype "passive"))
      (node (ref "C33") (pin "1") (pinfunction "1_1") (pintype "passive"))
      (node (ref "IC16") (pin "5") (pinfunction "AIN1_5") (pintype "input"))
      (node (ref "R29") (pin "2") (pinfunction "2_2") (pintype "passive"))
    )
    (net (code "63") (name "Net-(IC16-AIN2)") (class "Default")
      (node (ref "C30") (pin "2") (pinfunction "2_2") (pintype "passive"))
      (node (ref "C34") (pin "2") (pinfunction "2_2") (pintype "passive"))
      (node (ref "IC16") (pin "6") (pinfunction "AIN2_6") (pintype "input"))
      (node (ref "R30") (pin "2") (pinfunction "2_2") (pintype "passive"))
    )
    (net (code "64") (name "Net-(IC16-AIN3)") (class "Default")
      (node (ref "C29") (pin "2") (pinfunction "2_2") (pintype "passive"))
      (node (ref "C34") (pin "1") (pinfunction "1_1") (pintype "passive"))
      (node (ref "IC16") (pin "7") (pinfunction "AIN3_7") (pintype "input"))
      (node (ref "R31") (pin "2") (pinfunction "2_2") (pintype "passive"))
    )
    (net (code "65") (name "Net-(IC17-AIN0)") (class "Default")
      (node (ref "C38") (pin "2") (pinfunction "2_2") (pintype "passive"))
      (node (ref "C39") (pin "2") (pinfunction "2_2") (pintype "passive"))
      (node (ref "IC17") (pin "4") (pinfunction "AIN0_4") (pintype "input"))
      (node (ref "R32") (pin "2") (pinfunction "2_2") (pintype "passive"))
    )
    (net (code "66") (name "Net-(IC17-AIN1)") (class "Default")
      (node (ref "C37") (pin "2") (pinfunction "2_2") (pintype "passive"))
      (node (ref "C39") (pin "1") (pinfunction "1_1") (pintype "passive"))
      (node (ref "IC17") (pin "5") (pinfunction "AIN1_5") (pintype "input"))
      (node (ref "R33") (pin "2") (pinfunction "2_2") (pintype "passive"))
    )
    (net (code "67") (name "Net-(IC17-AIN2)") (class "Default")
      (node (ref "C36") (pin "2") (pinfunction "2_2") (pintype "passive"))
      (node (ref "C40") (pin "2") (pinfunction "2_2") (pintype "passive"))
      (node (ref "IC17") (pin "6") (pinfunction "AIN2_6") (pintype "input"))
      (node (ref "R34") (pin "2") (pinfunction "2_2") (pintype "passive"))
    )
    (net (code "68") (name "Net-(IC17-AIN3)") (class "Default")
      (node (ref "C35") (pin "2") (pinfunction "2_2") (pintype "passive"))
      (node (ref "C40") (pin "1") (pinfunction "1_1") (pintype "passive"))
      (node (ref "IC17") (pin "7") (pinfunction "AIN3_7") (pintype "input"))
      (node (ref "R35") (pin "2") (pinfunction "2_2") (pintype "passive"))
    )
    (net (code "69") (name "Net-(IC18-AIN0)") (class "Default")
      (node (ref "C42") (pin "2") (pinfunction "2_2") (pintype "passive"))
      (node (ref "C43") (pin "2") (pinfunction "2_2") (pintype "passive"))
      (node (ref "IC18") (pin "4") (pinfunction "AIN0_4") (pintype "input"))
      (node (ref "R36") (pin "2") (pinfunction "2_2") (pintype "passive"))
    )
    (net (code "70") (name "Net-(IC18-AIN1)") (class "Default")
      (node (ref "C41") (pin "2") (pinfunction "2_2") (pintype "passive"))
      (node (ref "C43") (pin "1") (pinfunction "1_1") (pintype "passive"))
      (node (ref "IC18") (pin "5") (pinfunction "AIN1_5") (pintype "input"))
      (node (ref "R37") (pin "2") (pinfunction "2_2") (pintype "passive"))
    )
    (net (code "71") (name "Net-(IC33A-C1+)") (class "Default")
      (node (ref "C6") (pin "1") (pinfunction "1_1") (pintype "passive"))
      (node (ref "IC33") (pin "1") (pinfunction "C1+_1") (pintype "bidirectional"))
    )
    (net (code "72") (name "Net-(IC33A-C1-)") (class "Default")
      (node (ref "C6") (pin "2") (pinfunction "2_2") (pintype "passive"))
      (node (ref "IC33") (pin "3") (pinfunction "C1-_3") (pintype "bidirectional"))
    )
    (net (code "73") (name "Net-(IC33A-C2+)") (class "Default")
      (node (ref "C7") (pin "1") (pinfunction "1_1") (pintype "passive"))
      (node (ref "IC33") (pin "4") (pinfunction "C2+_4") (pintype "bidirectional"))
    )
    (net (code "74") (name "Net-(IC33A-C2-)") (class "Default")
      (node (ref "C7") (pin "2") (pinfunction "2_2") (pintype "passive"))
      (node (ref "IC33") (pin "5") (pinfunction "C2-_5") (pintype "bidirectional"))
    )
    (net (code "75") (name "Net-(IC33A-R1IN)") (class "Default")
      (node (ref "IC33") (pin "13") (pinfunction "R1IN_13") (pintype "input"))
      (node (ref "SL5") (pin "2") (pinfunction "2_2") (pintype "passive"))
    )
    (net (code "76") (name "Net-(IC33A-T1OUT)") (class "Default")
      (node (ref "IC33") (pin "14") (pinfunction "T1OUT_14") (pintype "output"))
      (node (ref "SL5") (pin "3") (pinfunction "3_3") (pintype "passive"))
    )
    (net (code "77") (name "Net-(IC33A-V+)") (class "Default")
      (node (ref "C8") (pin "1") (pinfunction "1_1") (pintype "passive"))
      (node (ref "IC33") (pin "2") (pinfunction "V+_2") (pintype "bidirectional"))
    )
    (net (code "78") (name "Net-(IC33A-V-)") (class "Default")
      (node (ref "C9") (pin "2") (pinfunction "2_2") (pintype "passive"))
      (node (ref "IC33") (pin "6") (pinfunction "V-_6") (pintype "bidirectional"))
    )
    (net (code "79") (name "Net-(JP2-Pad1)") (class "Default")
      (node (ref "JP2") (pin "1") (pinfunction "1_1") (pintype "passive"))
      (node (ref "R5") (pin "1") (pinfunction "1_1") (pintype "passive"))
      (node (ref "R6") (pin "2") (pinfunction "2_2") (pintype "passive"))
    )
    (net (code "80") (name "Net-(L1-Pad1)") (class "Default")
      (node (ref "L1") (pin "1") (pinfunction "1_1") (pintype "passive"))
      (node (ref "X1") (pin "-1") (pinfunction "-1_-1") (pintype "passive"))
    )
    (net (code "81") (name "Net-(LED1-C)") (class "Default")
      (node (ref "LED1") (pin "3") (pinfunction "C_3") (pintype "passive"))
      (node (ref "R11") (pin "2") (pinfunction "2_2") (pintype "passive"))
    )
    (net (code "82") (name "Net-(Q2-G)") (class "Default")
      (node (ref "JP2") (pin "2") (pinfunction "2_2") (pintype "passive"))
      (node (ref "Q2") (pin "1") (pinfunction "G_1") (pintype "input"))
      (node (ref "Q3") (pin "1") (pinfunction "G_1") (pintype "input"))
      (node (ref "R1") (pin "1") (pinfunction "1_1") (pintype "passive"))
      (node (ref "R2") (pin "1") (pinfunction "1_1") (pintype "passive"))
    )
    (net (code "83") (name "Net-(Q2-S)") (class "Default")
      (node (ref "Q2") (pin "2") (pinfunction "S_2") (pintype "bidirectional"))
      (node (ref "R1") (pin "2") (pinfunction "2_2") (pintype "passive"))
      (node (ref "SL1") (pin "3") (pinfunction "3_3") (pintype "passive"))
      (node (ref "SL2") (pin "3") (pinfunction "3_3") (pintype "passive"))
    )
    (net (code "84") (name "Net-(Q3-S)") (class "Default")
      (node (ref "Q3") (pin "2") (pinfunction "S_2") (pintype "bidirectional"))
      (node (ref "R2") (pin "2") (pinfunction "2_2") (pintype "passive"))
      (node (ref "SL1") (pin "2") (pinfunction "2_2") (pintype "passive"))
      (node (ref "SL2") (pin "2") (pinfunction "2_2") (pintype "passive"))
    )
    (net (code "85") (name "Net-(R9-Pad1)") (class "Default")
      (node (ref "R9") (pin "1") (pinfunction "1_1") (pintype "passive"))
      (node (ref "T2") (pin "C") (pinfunction "C_C") (pintype "passive"))
    )
    (net (code "86") (name "Net-(R9-Pad2)") (class "Default")
      (node (ref "R9") (pin "2") (pinfunction "2_2") (pintype "passive"))
      (node (ref "T1") (pin "B") (pinfunction "B_B") (pintype "passive"))
    )
    (net (code "87") (name "Net-(R10-Pad2)") (class "Default")
      (node (ref "R10") (pin "2") (pinfunction "2_2") (pintype "passive"))
      (node (ref "T2") (pin "B") (pinfunction "B_B") (pintype "passive"))
    )
    (net (code "88") (name "Net-(R26-Pad1)") (class "Default")
      (node (ref "R26") (pin "1") (pinfunction "1_1") (pintype "passive"))
      (node (ref "SL9") (pin "3") (pinfunction "3_3") (pintype "passive"))
    )
    (net (code "89") (name "Net-(R40-Pad2)") (class "Default")
      (node (ref "R40") (pin "2") (pinfunction "2_2") (pintype "passive"))
      (node (ref "SL11") (pin "5") (pinfunction "5_5") (pintype "passive"))
    )
    (net (code "90") (name "SCK") (class "Default")
      (node (ref "IC10") (pin "3") (pinfunction "SCK_3") (pintype "input"))
      (node (ref "IC11") (pin "3") (pinfunction "SCK_3") (pintype "input"))
      (node (ref "IC12") (pin "3") (pinfunction "SCK_3") (pintype "input"))
      (node (ref "IC6") (pin "3") (pinfunction "SCK_3") (pintype "input"))
      (node (ref "IC7") (pin "3") (pinfunction "SCK_3") (pintype "input"))
      (node (ref "IC8") (pin "3") (pinfunction "SCK_3") (pintype "input"))
      (node (ref "IC9") (pin "3") (pinfunction "SCK_3") (pintype "input"))
      (node (ref "JP6") (pin "12") (pinfunction "12_12") (pintype "passive"))
    )
    (net (code "91") (name "SCL2") (class "Default")
      (node (ref "IC1") (pin "11") (pinfunction "PD7(AIN1)_11") (pintype "bidirectional"))
      (node (ref "IC15") (pin "10") (pinfunction "SCL_10") (pintype "input"))
      (node (ref "IC16") (pin "10") (pinfunction "SCL_10") (pintype "input"))
      (node (ref "IC17") (pin "1") (pinfunction "ADDR_1") (pintype "input"))
      (node (ref "IC17") (pin "10") (pinfunction "SCL_10") (pintype "input"))
      (node (ref "IC18") (pin "10") (pinfunction "SCL_10") (pintype "input"))
      (node (ref "R41") (pin "1") (pinfunction "1_1") (pintype "passive"))
      (node (ref "R42") (pin "2") (pinfunction "2_2") (pintype "passive"))
    )
    (net (code "92") (name "SDA2") (class "Default")
      (node (ref "IC1") (pin "10") (pinfunction "PD6(AIN0)_10") (pintype "bidirectional"))
      (node (ref "IC15") (pin "9") (pinfunction "SDA_9") (pintype "bidirectional"))
      (node (ref "IC16") (pin "9") (pinfunction "SDA_9") (pintype "bidirectional"))
      (node (ref "IC17") (pin "9") (pinfunction "SDA_9") (pintype "bidirectional"))
      (node (ref "IC18") (pin "1") (pinfunction "ADDR_1") (pintype "input"))
      (node (ref "IC18") (pin "9") (pinfunction "SDA_9") (pintype "bidirectional"))
      (node (ref "R43") (pin "2") (pinfunction "2_2") (pintype "passive"))
      (node (ref "R44") (pin "1") (pinfunction "1_1") (pintype "passive"))
    )
    (net (code "93") (name "SDI") (class "Default")
      (node (ref "IC10") (pin "4") (pinfunction "SDI_4") (pintype "input"))
      (node (ref "IC11") (pin "4") (pinfunction "SDI_4") (pintype "input"))
      (node (ref "IC12") (pin "4") (pinfunction "SDI_4") (pintype "input"))
      (node (ref "IC6") (pin "4") (pinfunction "SDI_4") (pintype "input"))
      (node (ref "IC7") (pin "4") (pinfunction "SDI_4") (pintype "input"))
      (node (ref "IC8") (pin "4") (pinfunction "SDI_4") (pintype "input"))
      (node (ref "IC9") (pin "4") (pinfunction "SDI_4") (pintype "input"))
      (node (ref "JP6") (pin "9") (pinfunction "9_9") (pintype "passive"))
    )
    (net (code "94") (name "SFET1") (class "Default")
      (node (ref "IC14") (pin "8") (pinfunction "OUT_8") (pintype "output"))
      (node (ref "R24") (pin "2") (pinfunction "2_2") (pintype "passive"))
      (node (ref "SL4") (pin "3") (pinfunction "3_3") (pintype "passive"))
    )
    (net (code "95") (name "SFET2") (class "Default")
      (node (ref "IC14") (pin "1") (pinfunction "OUT_1") (pintype "output"))
      (node (ref "R20") (pin "2") (pinfunction "2_2") (pintype "passive"))
      (node (ref "SL4") (pin "2") (pinfunction "2_2") (pintype "passive"))
    )
    (net (code "96") (name "SFET3") (class "Default")
      (node (ref "IC14") (pin "14") (pinfunction "OUT_14") (pintype "output"))
      (node (ref "R22") (pin "2") (pinfunction "2_2") (pintype "passive"))
      (node (ref "SL4") (pin "1") (pinfunction "1_1") (pintype "passive"))
    )
    (net (code "97") (name "SFET4") (class "Default")
      (node (ref "IC13") (pin "7") (pinfunction "OUT_7") (pintype "output"))
      (node (ref "R666") (pin "2") (pinfunction "2_2") (pintype "passive"))
      (node (ref "SL3") (pin "4") (pinfunction "4_4") (pintype "passive"))
    )
    (net (code "98") (name "SFET5") (class "Default")
      (node (ref "IC13") (pin "8") (pinfunction "OUT_8") (pintype "output"))
      (node (ref "R16") (pin "2") (pinfunction "2_2") (pintype "passive"))
      (node (ref "SL3") (pin "3") (pinfunction "3_3") (pintype "passive"))
    )
    (net (code "99") (name "SFET6") (class "Default")
      (node (ref "IC13") (pin "1") (pinfunction "OUT_1") (pintype "output"))
      (node (ref "R14") (pin "2") (pinfunction "2_2") (pintype "passive"))
      (node (ref "SL3") (pin "2") (pinfunction "2_2") (pintype "passive"))
    )
    (net (code "100") (name "SFET7") (class "Default")
      (node (ref "IC13") (pin "14") (pinfunction "OUT_14") (pintype "output"))
      (node (ref "R18") (pin "2") (pinfunction "2_2") (pintype "passive"))
      (node (ref "SL3") (pin "1") (pinfunction "1_1") (pintype "passive"))
    )
    (net (code "101") (name "U") (class "Default")
      (node (ref "C22") (pin "1") (pinfunction "1_1") (pintype "passive"))
      (node (ref "IC18") (pin "6") (pinfunction "AIN2_6") (pintype "input"))
      (node (ref "R38") (pin "1") (pinfunction "1_1") (pintype "passive"))
      (node (ref "R39") (pin "1") (pinfunction "1_1") (pintype "passive"))
      (node (ref "R40") (pin "1") (pinfunction "1_1") (pintype "passive"))
    )
    (net (code "102") (name "VDD") (class "Default")
      (node (ref "C10") (pin "1") (pinfunction "1_1") (pintype "passive"))
      (node (ref "C11") (pin "1") (pinfunction "1_1") (pintype "passive"))
      (node (ref "C12") (pin "1") (pinfunction "1_1") (pintype "passive"))
      (node (ref "C13") (pin "1") (pinfunction "1_1") (pintype "passive"))
      (node (ref "C14") (pin "1") (pinfunction "1_1") (pintype "passive"))
      (node (ref "C15") (pin "1") (pinfunction "1_1") (pintype "passive"))
      (node (ref "C16") (pin "1") (pinfunction "1_1") (pintype "passive"))
      (node (ref "C17") (pin "1") (pinfunction "1_1") (pintype "passive"))
      (node (ref "C18") (pin "1") (pinfunction "1_1") (pintype "passive"))
      (node (ref "C2") (pin "1") (pinfunction "1_1") (pintype "passive"))
      (node (ref "C44") (pin "1") (pinfunction "1_1") (pintype "passive"))
      (node (ref "C45") (pin "1") (pinfunction "1_1") (pintype "passive"))
      (node (ref "C8") (pin "2") (pinfunction "2_2") (pintype "passive"))
      (node (ref "IC10") (pin "1") (pinfunction "VDD_1") (pintype "power_in"))
      (node (ref "IC10") (pin "6") (pinfunction "~{SHDN}_6") (pintype "input"))
      (node (ref "IC11") (pin "1") (pinfunction "VDD_1") (pintype "power_in"))
      (node (ref "IC11") (pin "6") (pinfunction "~{SHDN}_6") (pintype "input"))
      (node (ref "IC12") (pin "1") (pinfunction "VDD_1") (pintype "power_in"))
      (node (ref "IC12") (pin "6") (pinfunction "~{SHDN}_6") (pintype "input"))
      (node (ref "IC15") (pin "1") (pinfunction "ADDR_1") (pintype "input"))
      (node (ref "IC15") (pin "8") (pinfunction "VDD_8") (pintype "power_in"))
      (node (ref "IC16") (pin "8") (pinfunction "VDD_8") (pintype "power_in"))
      (node (ref "IC17") (pin "8") (pinfunction "VDD_8") (pintype "power_in"))
      (node (ref "IC18") (pin "8") (pinfunction "VDD_8") (pintype "power_in"))
      (node (ref "IC33") (pin "15") (pinfunction "GND_15") (pintype "power_in"))
      (node (ref "IC33") (pin "16") (pinfunction "VCC_16") (pintype "power_in"))
      (node (ref "IC4") (pin "OUT") (pinfunction "OUT_OUT") (pintype "passive"))
      (node (ref "IC6") (pin "1") (pinfunction "VDD_1") (pintype "power_in"))
      (node (ref "IC6") (pin "6") (pinfunction "~{SHDN}_6") (pintype "input"))
      (node (ref "IC7") (pin "1") (pinfunction "VDD_1") (pintype "power_in"))
      (node (ref "IC7") (pin "6") (pinfunction "~{SHDN}_6") (pintype "input"))
      (node (ref "IC8") (pin "1") (pinfunction "VDD_1") (pintype "power_in"))
      (node (ref "IC8") (pin "6") (pinfunction "~{SHDN}_6") (pintype "input"))
      (node (ref "IC9") (pin "1") (pinfunction "VDD_1") (pintype "power_in"))
      (node (ref "IC9") (pin "6") (pinfunction "~{SHDN}_6") (pintype "input"))
      (node (ref "JP1") (pin "1") (pinfunction "1_1") (pintype "passive"))
      (node (ref "JP2") (pin "3") (pinfunction "3_3") (pintype "passive"))
      (node (ref "JP7") (pin "4") (pinfunction "4_4") (pintype "passive"))
      (node (ref "LED1") (pin "1") (pinfunction "A_1") (pintype "passive"))
      (node (ref "R3") (pin "1") (pinfunction "1_1") (pintype "passive"))
      (node (ref "R4") (pin "1") (pinfunction "1_1") (pintype "passive"))
      (node (ref "R42") (pin "1") (pinfunction "1_1") (pintype "passive"))
      (node (ref "R43") (pin "1") (pinfunction "1_1") (pintype "passive"))
      (node (ref "R5") (pin "2") (pinfunction "2_2") (pintype "passive"))
    )
    (net (code "103") (name "VREF") (class "Default")
      (node (ref "IC13") (pin "10") (pinfunction "+IN_10") (pintype "input"))
      (node (ref "IC13") (pin "12") (pinfunction "+IN_12") (pintype "input"))
      (node (ref "IC13") (pin "3") (pinfunction "+IN_3") (pintype "input"))
      (node (ref "IC13") (pin "5") (pinfunction "+IN_5") (pintype "input"))
      (node (ref "IC14") (pin "10") (pinfunction "+IN_10") (pintype "input"))
      (node (ref "IC14") (pin "12") (pinfunction "+IN_12") (pintype "input"))
      (node (ref "IC14") (pin "3") (pinfunction "+IN_3") (pintype "input"))
      (node (ref "R7") (pin "2") (pinfunction "2_2") (pintype "passive"))
      (node (ref "R8") (pin "1") (pinfunction "1_1") (pintype "passive"))
    )
    (net (code "104") (name "unconnected-(IC1-ADC6-Pad19)") (class "Default")
      (node (ref "IC1") (pin "19") (pinfunction "ADC6_19") (pintype "bidirectional"))
    )
    (net (code "105") (name "unconnected-(IC1-ADC7-Pad22)") (class "Default")
      (node (ref "IC1") (pin "22") (pinfunction "ADC7_22") (pintype "bidirectional"))
    )
    (net (code "106") (name "unconnected-(IC15-ALERT{slash}RDY-Pad2)") (class "Default")
      (node (ref "IC15") (pin "2") (pinfunction "ALERT/RDY_2") (pintype "input"))
    )
    (net (code "107") (name "unconnected-(IC16-ALERT{slash}RDY-Pad2)") (class "Default")
      (node (ref "IC16") (pin "2") (pinfunction "ALERT/RDY_2") (pintype "input"))
    )
    (net (code "108") (name "unconnected-(IC17-ALERT{slash}RDY-Pad2)") (class "Default")
      (node (ref "IC17") (pin "2") (pinfunction "ALERT/RDY_2") (pintype "input"))
    )
    (net (code "109") (name "unconnected-(IC18-ALERT{slash}RDY-Pad2)") (class "Default")
      (node (ref "IC18") (pin "2") (pinfunction "ALERT/RDY_2") (pintype "input"))
    )
    (net (code "110") (name "unconnected-(IC33A-R2OUT-Pad9)") (class "Default")
      (node (ref "IC33") (pin "9") (pinfunction "R2OUT_9") (pintype "output"))
    )
    (net (code "111") (name "unconnected-(IC33A-T2OUT-Pad7)") (class "Default")
      (node (ref "IC33") (pin "7") (pinfunction "T2OUT_7") (pintype "output"))
    )
    (net (code "112") (name "unconnected-(JP6-Pad7)") (class "Default")
      (node (ref "JP6") (pin "7") (pinfunction "7_7") (pintype "passive"))
    )
    (net (code "113") (name "unconnected-(JP6-Pad8)") (class "Default")
      (node (ref "JP6") (pin "8") (pinfunction "8_8") (pintype "passive"))
    )
    (net (code "114") (name "unconnected-(X1-Pad-2)") (class "Default")
      (node (ref "X1") (pin "-2") (pinfunction "-2_-2") (pintype "passive"))
    )
  )
)
